# LB_BIT_i13_LIGHTSENSOR-v03_5_5.net
KiCad netlist of a schematic drawn in EAGLE
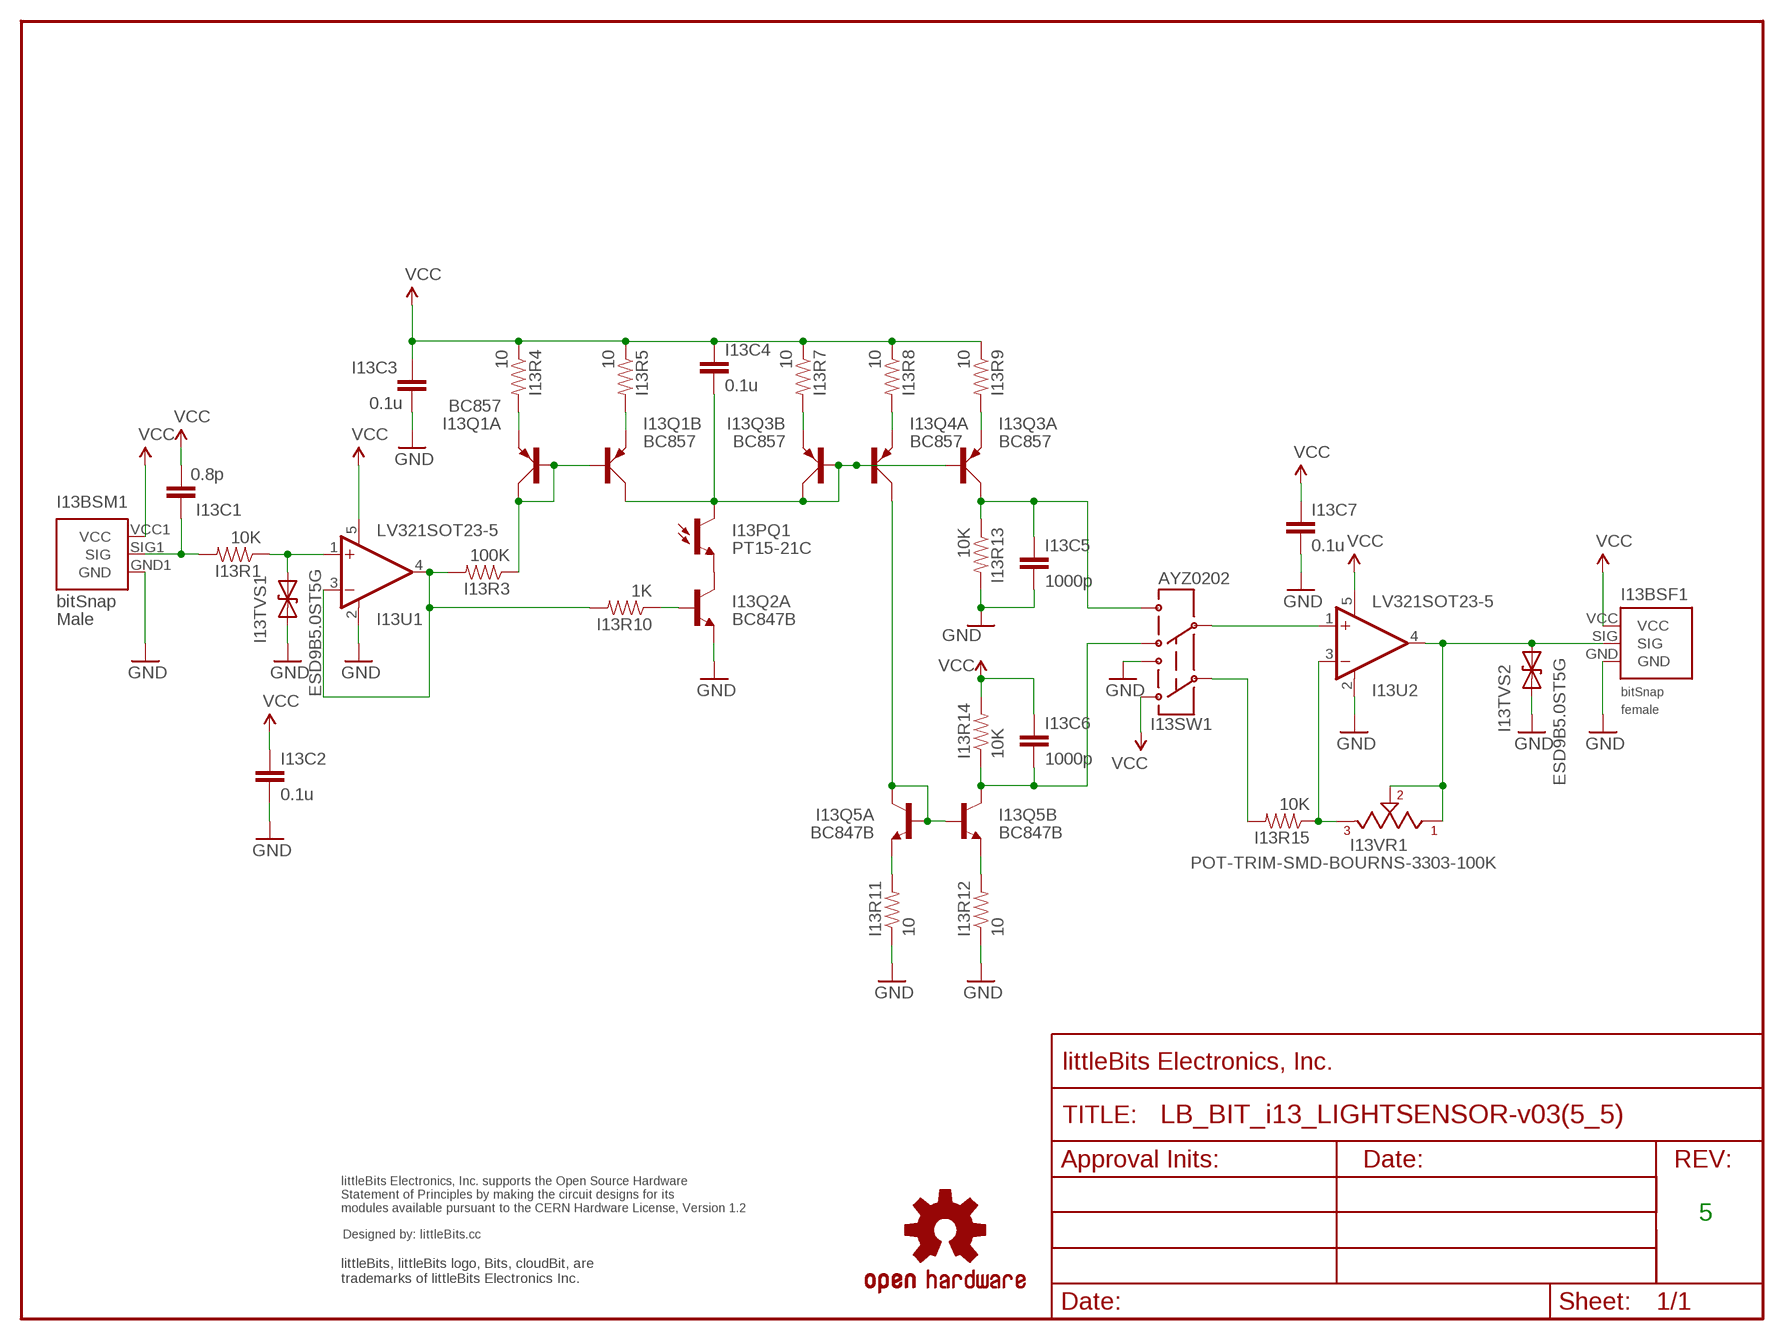
[diagram p0: schematic, sheet 1]

(export (version "E")
  (design (tool "Eeschema 10.0.6"))
  (components
    (comp (ref "I13BSF1")
      (value "BITSNAP_V03_FEMALE")
      (footprint "eagle-import:BITSNAP_V03_FEMALE")
      (libsource (lib "eagle-import") (part "BITSNAP_V03_FEMALE"))
    )
    (comp (ref "I13BSM1")
      (value "BITSNAP_V03_MALE")
      (footprint "eagle-import:BITSNAP_V03_MALE")
      (libsource (lib "eagle-import") (part "BITSNAP_V03_MALE"))
    )
    (comp (ref "I13C1")
      (value "0.8p")
      (footprint "eagle-import:CAP-0603")
      (libsource (lib "eagle-import") (part "CAPCAP-0603"))
    )
    (comp (ref "I13C2")
      (value "0.1u")
      (footprint "eagle-import:CAP-0603")
      (libsource (lib "eagle-import") (part "CAPCAP-0603"))
    )
    (comp (ref "I13C3")
      (value "0.1u")
      (footprint "eagle-import:CAP-0603")
      (libsource (lib "eagle-import") (part "CAPCAP-0603"))
    )
    (comp (ref "I13C4")
      (value "0.1u")
      (footprint "eagle-import:CAP-0603")
      (libsource (lib "eagle-import") (part "CAPCAP-0603"))
    )
    (comp (ref "I13C5")
      (value "1000p")
      (footprint "eagle-import:CAP-0603")
      (libsource (lib "eagle-import") (part "CAPCAP-0603"))
    )
    (comp (ref "I13C6")
      (value "1000p")
      (footprint "eagle-import:CAP-0603")
      (libsource (lib "eagle-import") (part "CAPCAP-0603"))
    )
    (comp (ref "I13C7")
      (value "0.1u")
      (footprint "eagle-import:CAP-0603")
      (libsource (lib "eagle-import") (part "CAPCAP-0603"))
    )
    (comp (ref "I13PQ1")
      (value "PT15-21C")
      (footprint "eagle-import:PHOTOTRANS-1206")
      (libsource (lib "eagle-import") (part "TRANS-PHOTO"))
    )
    (comp (ref "I13Q1")
      (value "BC857")
      (footprint "eagle-import:SOT-363_PHILLIPS")
      (libsource (lib "eagle-import") (part "TRANS-BJT_PNP-DUALBC857"))
    )
    (comp (ref "I13Q2")
      (value "BC847B")
      (footprint "eagle-import:SOT-363_PHILLIPS")
      (libsource (lib "eagle-import") (part "TRANS-BJT_NPN-DUAL-BC847BS"))
    )
    (comp (ref "I13Q3")
      (value "BC857")
      (footprint "eagle-import:SOT-363_PHILLIPS")
      (libsource (lib "eagle-import") (part "TRANS-BJT_PNP-DUALBC857"))
    )
    (comp (ref "I13Q4")
      (value "BC857")
      (footprint "eagle-import:SOT-363_PHILLIPS")
      (libsource (lib "eagle-import") (part "TRANS-BJT_PNP-DUALBC857"))
    )
    (comp (ref "I13Q5")
      (value "BC847B")
      (footprint "eagle-import:SOT-363_PHILLIPS")
      (libsource (lib "eagle-import") (part "TRANS-BJT_NPN-DUAL-BC847BS"))
    )
    (comp (ref "I13R1")
      (value "10K")
      (footprint "eagle-import:RES-0603")
      (libsource (lib "eagle-import") (part "RESISTOR0603"))
    )
    (comp (ref "I13R3")
      (value "100K")
      (footprint "eagle-import:RES-0603")
      (libsource (lib "eagle-import") (part "RESISTOR0603"))
    )
    (comp (ref "I13R4")
      (value "10")
      (footprint "eagle-import:RES-0603")
      (libsource (lib "eagle-import") (part "RESISTOR0603"))
    )
    (comp (ref "I13R5")
      (value "10")
      (footprint "eagle-import:RES-0603")
      (libsource (lib "eagle-import") (part "RESISTOR0603"))
    )
    (comp (ref "I13R7")
      (value "10")
      (footprint "eagle-import:RES-0603")
      (libsource (lib "eagle-import") (part "RESISTOR0603"))
    )
    (comp (ref "I13R8")
      (value "10")
      (footprint "eagle-import:RES-0603")
      (libsource (lib "eagle-import") (part "RESISTOR0603"))
    )
    (comp (ref "I13R9")
      (value "10")
      (footprint "eagle-import:RES-0603")
      (libsource (lib "eagle-import") (part "RESISTOR0603"))
    )
    (comp (ref "I13R10")
      (value "1K")
      (footprint "eagle-import:RES-0603")
      (libsource (lib "eagle-import") (part "RESISTOR0603"))
    )
    (comp (ref "I13R11")
      (value "10")
      (footprint "eagle-import:RES-0603")
      (libsource (lib "eagle-import") (part "RESISTOR0603"))
    )
    (comp (ref "I13R12")
      (value "10")
      (footprint "eagle-import:RES-0603")
      (libsource (lib "eagle-import") (part "RESISTOR0603"))
    )
    (comp (ref "I13R13")
      (value "10K")
      (footprint "eagle-import:RES-0603")
      (libsource (lib "eagle-import") (part "RESISTOR0603"))
    )
    (comp (ref "I13R14")
      (value "10K")
      (footprint "eagle-import:RES-0603")
      (libsource (lib "eagle-import") (part "RESISTOR0603"))
    )
    (comp (ref "I13R15")
      (value "10K")
      (footprint "eagle-import:RES-0603")
      (libsource (lib "eagle-import") (part "RES-0603"))
    )
    (comp (ref "I13SW1")
      (value "AYZ0202")
      (footprint "eagle-import:AYZ0202")
      (libsource (lib "eagle-import") (part "AYZ0202"))
    )
    (comp (ref "I13TVS1")
      (value "ESD9B5.0ST5G")
      (footprint "eagle-import:SOD-923")
      (libsource (lib "eagle-import") (part "DIODE-TVSSOD-923"))
    )
    (comp (ref "I13TVS2")
      (value "ESD9B5.0ST5G")
      (footprint "eagle-import:SOD-923")
      (libsource (lib "eagle-import") (part "DIODE-TVSSOD-923"))
    )
    (comp (ref "I13U1")
      (value "LV321SOT23-5")
      (footprint "eagle-import:SOT23-5")
      (libsource (lib "eagle-import") (part "LV321SOT23-5"))
    )
    (comp (ref "I13U2")
      (value "LV321SOT23-5")
      (footprint "eagle-import:SOT23-5")
      (libsource (lib "eagle-import") (part "LV321SOT23-5"))
    )
    (comp (ref "I13VR1")
      (value "POT-TRIM-SMD-BOURNS-3303-100K")
      (footprint "eagle-import:POT-TRIM-SMD-BOURNS-3303")
      (libsource (lib "eagle-import") (part "POT-TRIM-SMD-BOURNS-3303"))
    )
    (comp (ref "U$1")
      (value "OSHWCREDIT")
      (footprint "eagle-import:OSHWCREDIT")
      (libsource (lib "eagle-import") (part "OSHWCREDIT"))
    )
    (comp (ref "U$2")
      (value "OSHW-LOGOL")
      (footprint "eagle-import:OSHW-LOGO-L")
      (libsource (lib "eagle-import") (part "OSHW-LOGOL"))
    )
    (comp (ref "U$3")
      (value "FRAME-LETTER-OHWOHW")
      (footprint "eagle-import:FABDWG01-OHW")
      (libsource (lib "eagle-import") (part "FRAME-LETTER-OHWOHW"))
    )
  )
  (nets
    (net (code "1") (name "GND") (class "Default")
      (node (ref "I13BSF1") (pin "GND") (pinfunction "GND_GND") (pintype "bidirectional"))
      (node (ref "I13BSM1") (pin "GND1") (pinfunction "GND_GND1") (pintype "bidirectional"))
      (node (ref "I13C2") (pin "2") (pinfunction "2_2") (pintype "passive"))
      (node (ref "I13C3") (pin "2") (pinfunction "2_2") (pintype "passive"))
      (node (ref "I13C5") (pin "2") (pinfunction "2_2") (pintype "passive"))
      (node (ref "I13C7") (pin "2") (pinfunction "2_2") (pintype "passive"))
      (node (ref "I13Q2") (pin "1") (pinfunction "E_1") (pintype "passive"))
      (node (ref "I13R11") (pin "1") (pinfunction "1_1") (pintype "passive"))
      (node (ref "I13R12") (pin "1") (pinfunction "1_1") (pintype "passive"))
      (node (ref "I13R13") (pin "2") (pinfunction "2_2") (pintype "passive"))
      (node (ref "I13SW1") (pin "3") (pinfunction "3_3") (pintype "bidirectional"))
      (node (ref "I13TVS1") (pin "1") (pinfunction "A_1") (pintype "passive"))
      (node (ref "I13TVS2") (pin "1") (pinfunction "A_1") (pintype "passive"))
      (node (ref "I13U1") (pin "2") (pinfunction "V-_2") (pintype "power_in"))
      (node (ref "I13U2") (pin "2") (pinfunction "V-_2") (pintype "power_in"))
    )
    (net (code "2") (name "Net-(I13BSM1-SIG)") (class "Default")
      (node (ref "I13BSM1") (pin "SIG1") (pinfunction "SIG_SIG1") (pintype "bidirectional"))
      (node (ref "I13C1") (pin "1") (pinfunction "1_1") (pintype "passive"))
      (node (ref "I13R1") (pin "2") (pinfunction "2_2") (pintype "passive"))
    )
    (net (code "3") (name "Net-(I13Q1A-B)") (class "Default")
      (node (ref "I13Q1") (pin "2") (pinfunction "B_2") (pintype "passive"))
      (node (ref "I13Q1") (pin "5") (pinfunction "B_5") (pintype "passive"))
      (node (ref "I13Q1") (pin "6") (pinfunction "C_6") (pintype "passive"))
      (node (ref "I13R3") (pin "1") (pinfunction "1_1") (pintype "passive"))
    )
    (net (code "4") (name "Net-(I13Q1A-E)") (class "Default")
      (node (ref "I13Q1") (pin "1") (pinfunction "E_1") (pintype "passive"))
      (node (ref "I13R4") (pin "2") (pinfunction "2_2") (pintype "passive"))
    )
    (net (code "5") (name "Net-(I13Q1B-C)") (class "Default")
      (node (ref "I13C4") (pin "2") (pinfunction "2_2") (pintype "passive"))
      (node (ref "I13PQ1") (pin "C") (pinfunction "C_C") (pintype "passive"))
      (node (ref "I13Q1") (pin "3") (pinfunction "C_3") (pintype "passive"))
      (node (ref "I13Q3") (pin "2") (pinfunction "B_2") (pintype "passive"))
      (node (ref "I13Q3") (pin "3") (pinfunction "C_3") (pintype "passive"))
      (node (ref "I13Q3") (pin "5") (pinfunction "B_5") (pintype "passive"))
      (node (ref "I13Q4") (pin "2") (pinfunction "B_2") (pintype "passive"))
    )
    (net (code "6") (name "Net-(I13Q1B-E)") (class "Default")
      (node (ref "I13Q1") (pin "4") (pinfunction "E_4") (pintype "passive"))
      (node (ref "I13R5") (pin "2") (pinfunction "2_2") (pintype "passive"))
    )
    (net (code "7") (name "Net-(I13Q2A-B)") (class "Default")
      (node (ref "I13Q2") (pin "2") (pinfunction "B_2") (pintype "passive"))
      (node (ref "I13R10") (pin "1") (pinfunction "1_1") (pintype "passive"))
    )
    (net (code "8") (name "Net-(I13Q2A-C)") (class "Default")
      (node (ref "I13PQ1") (pin "E") (pinfunction "E_E") (pintype "passive"))
      (node (ref "I13Q2") (pin "6") (pinfunction "C_6") (pintype "passive"))
    )
    (net (code "9") (name "Net-(I13Q3A-C)") (class "Default")
      (node (ref "I13C5") (pin "1") (pinfunction "1_1") (pintype "passive"))
      (node (ref "I13Q3") (pin "6") (pinfunction "C_6") (pintype "passive"))
      (node (ref "I13R13") (pin "1") (pinfunction "1_1") (pintype "passive"))
      (node (ref "I13SW1") (pin "6") (pinfunction "6_6") (pintype "bidirectional"))
    )
    (net (code "10") (name "Net-(I13Q3A-E)") (class "Default")
      (node (ref "I13Q3") (pin "1") (pinfunction "E_1") (pintype "passive"))
      (node (ref "I13R9") (pin "2") (pinfunction "2_2") (pintype "passive"))
    )
    (net (code "11") (name "Net-(I13Q3B-E)") (class "Default")
      (node (ref "I13Q3") (pin "4") (pinfunction "E_4") (pintype "passive"))
      (node (ref "I13R7") (pin "2") (pinfunction "2_2") (pintype "passive"))
    )
    (net (code "12") (name "Net-(I13Q4A-C)") (class "Default")
      (node (ref "I13Q4") (pin "6") (pinfunction "C_6") (pintype "passive"))
      (node (ref "I13Q5") (pin "2") (pinfunction "B_2") (pintype "passive"))
      (node (ref "I13Q5") (pin "5") (pinfunction "B_5") (pintype "passive"))
      (node (ref "I13Q5") (pin "6") (pinfunction "C_6") (pintype "passive"))
    )
    (net (code "13") (name "Net-(I13Q4A-E)") (class "Default")
      (node (ref "I13Q4") (pin "1") (pinfunction "E_1") (pintype "passive"))
      (node (ref "I13R8") (pin "2") (pinfunction "2_2") (pintype "passive"))
    )
    (net (code "14") (name "Net-(I13Q5A-E)") (class "Default")
      (node (ref "I13Q5") (pin "1") (pinfunction "E_1") (pintype "passive"))
      (node (ref "I13R11") (pin "2") (pinfunction "2_2") (pintype "passive"))
    )
    (net (code "15") (name "Net-(I13Q5B-C)") (class "Default")
      (node (ref "I13C6") (pin "2") (pinfunction "2_2") (pintype "passive"))
      (node (ref "I13Q5") (pin "3") (pinfunction "C_3") (pintype "passive"))
      (node (ref "I13R14") (pin "1") (pinfunction "1_1") (pintype "passive"))
      (node (ref "I13SW1") (pin "4") (pinfunction "4_4") (pintype "bidirectional"))
    )
    (net (code "16") (name "Net-(I13Q5B-E)") (class "Default")
      (node (ref "I13Q5") (pin "4") (pinfunction "E_4") (pintype "passive"))
      (node (ref "I13R12") (pin "2") (pinfunction "2_2") (pintype "passive"))
    )
    (net (code "17") (name "Net-(I13R15-Pad2)") (class "Default")
      (node (ref "I13R15") (pin "2") (pinfunction "2_2") (pintype "passive"))
      (node (ref "I13SW1") (pin "2") (pinfunction "2_2") (pintype "bidirectional"))
    )
    (net (code "18") (name "Net-(I13TVS1-C)") (class "Default")
      (node (ref "I13R1") (pin "1") (pinfunction "1_1") (pintype "passive"))
      (node (ref "I13TVS1") (pin "2") (pinfunction "C_2") (pintype "passive"))
      (node (ref "I13U1") (pin "1") (pinfunction "+IN_1") (pintype "input"))
    )
    (net (code "19") (name "Net-(I13TVS2-C)") (class "Default")
      (node (ref "I13BSF1") (pin "SIG") (pinfunction "SIG_SIG") (pintype "bidirectional"))
      (node (ref "I13TVS2") (pin "2") (pinfunction "C_2") (pintype "passive"))
      (node (ref "I13U2") (pin "4") (pinfunction "OUT_4") (pintype "output"))
      (node (ref "I13VR1") (pin "1") (pinfunction "1_1") (pintype "passive"))
      (node (ref "I13VR1") (pin "2") (pinfunction "2_2") (pintype "passive"))
    )
    (net (code "20") (name "Net-(I13U1--IN)") (class "Default")
      (node (ref "I13R10") (pin "2") (pinfunction "2_2") (pintype "passive"))
      (node (ref "I13R3") (pin "2") (pinfunction "2_2") (pintype "passive"))
      (node (ref "I13U1") (pin "3") (pinfunction "-IN_3") (pintype "input"))
      (node (ref "I13U1") (pin "4") (pinfunction "OUT_4") (pintype "output"))
    )
    (net (code "21") (name "Net-(I13U2-+IN)") (class "Default")
      (node (ref "I13SW1") (pin "5") (pinfunction "5_5") (pintype "bidirectional"))
      (node (ref "I13U2") (pin "1") (pinfunction "+IN_1") (pintype "input"))
    )
    (net (code "22") (name "Net-(I13U2--IN)") (class "Default")
      (node (ref "I13R15") (pin "1") (pinfunction "1_1") (pintype "passive"))
      (node (ref "I13U2") (pin "3") (pinfunction "-IN_3") (pintype "input"))
      (node (ref "I13VR1") (pin "3") (pinfunction "3_3") (pintype "passive"))
    )
    (net (code "23") (name "VCC") (class "Default")
      (node (ref "I13BSF1") (pin "VCC") (pinfunction "VCC_VCC") (pintype "bidirectional"))
      (node (ref "I13BSM1") (pin "VCC1") (pinfunction "VCC_VCC1") (pintype "bidirectional"))
      (node (ref "I13C1") (pin "2") (pinfunction "2_2") (pintype "passive"))
      (node (ref "I13C2") (pin "1") (pinfunction "1_1") (pintype "passive"))
      (node (ref "I13C3") (pin "1") (pinfunction "1_1") (pintype "passive"))
      (node (ref "I13C4") (pin "1") (pinfunction "1_1") (pintype "passive"))
      (node (ref "I13C6") (pin "1") (pinfunction "1_1") (pintype "passive"))
      (node (ref "I13C7") (pin "1") (pinfunction "1_1") (pintype "passive"))
      (node (ref "I13R14") (pin "2") (pinfunction "2_2") (pintype "passive"))
      (node (ref "I13R4") (pin "1") (pinfunction "1_1") (pintype "passive"))
      (node (ref "I13R5") (pin "1") (pinfunction "1_1") (pintype "passive"))
      (node (ref "I13R7") (pin "1") (pinfunction "1_1") (pintype "passive"))
      (node (ref "I13R8") (pin "1") (pinfunction "1_1") (pintype "passive"))
      (node (ref "I13R9") (pin "1") (pinfunction "1_1") (pintype "passive"))
      (node (ref "I13SW1") (pin "1") (pinfunction "1_1") (pintype "bidirectional"))
      (node (ref "I13U1") (pin "5") (pinfunction "V+_5") (pintype "power_in"))
      (node (ref "I13U2") (pin "5") (pinfunction "V+_5") (pintype "power_in"))
    )
  )
)
